# MkI.net
KiCad netlist of a schematic drawn in EAGLE
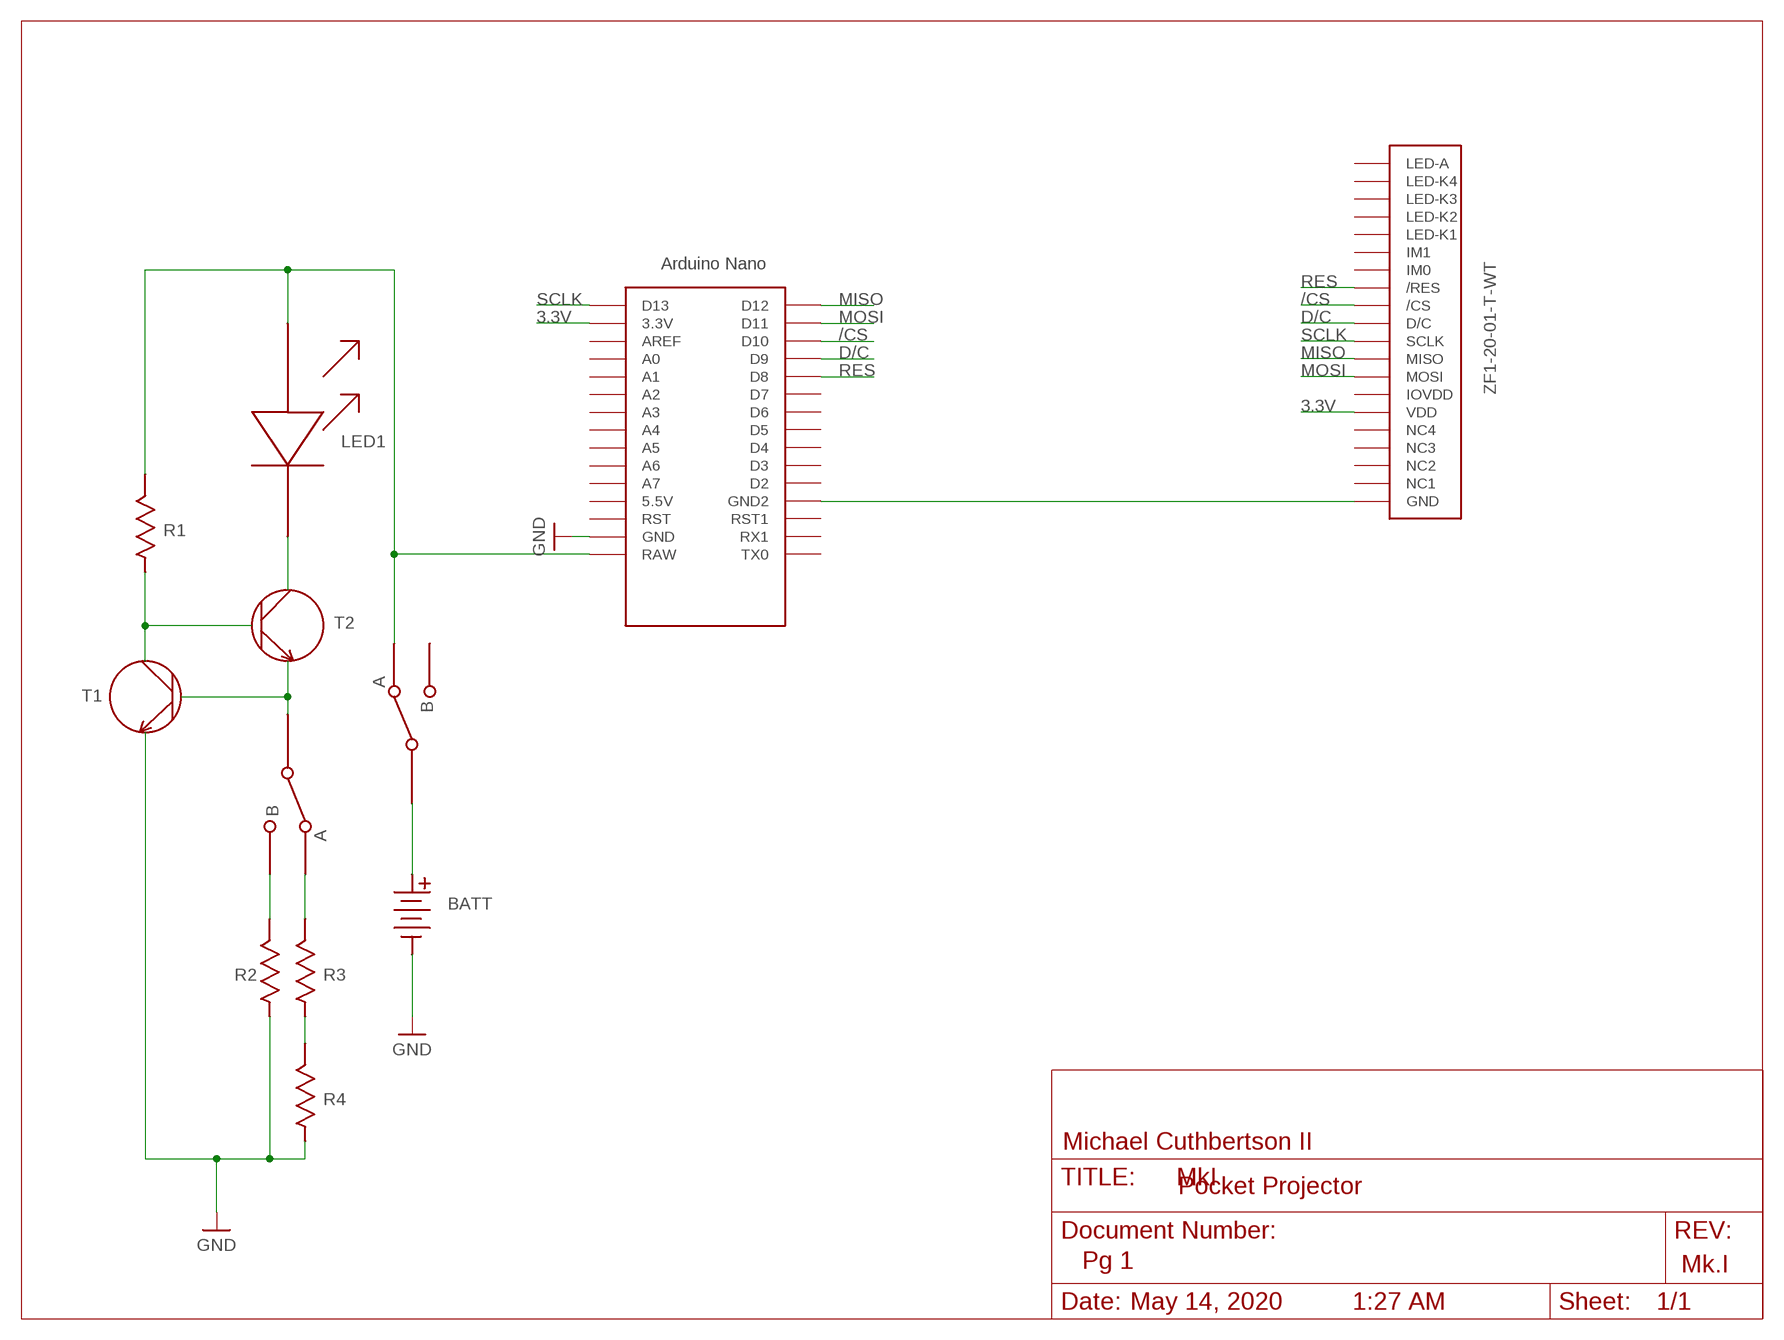
[diagram p0: schematic, sheet 1]

(export (version "E")
  (design (tool "Eeschema 10.0.6"))
  (components
    (comp (ref "R1")
      (value "2.2k")
      (footprint "eagle-import:ERJ1T")
      (libsource (lib "eagle-import") (part "ERJ1T"))
    )
    (comp (ref "R2")
      (value "130")
      (footprint "eagle-import:CRCW2512")
      (libsource (lib "eagle-import") (part "CRCW2512"))
    )
    (comp (ref "R3")
      (value "200")
      (footprint "eagle-import:CRCW2512")
      (libsource (lib "eagle-import") (part "CRCW2512"))
    )
    (comp (ref "R4")
      (value "200")
      (footprint "eagle-import:CRCW2512")
      (libsource (lib "eagle-import") (part "CRCW2512"))
    )
    (comp (ref "S1")
      (value "A107673-ND")
      (footprint "eagle-import:A107673-ND")
      (libsource (lib "eagle-import") (part "A107673-ND"))
    )
    (comp (ref "S2")
      (value "A107673-ND")
      (footprint "eagle-import:A107673-ND")
      (libsource (lib "eagle-import") (part "A107673-ND"))
    )
    (comp (ref "T1")
      (value "BC547")
      (footprint "eagle-import:BC547")
      (libsource (lib "eagle-import") (part "BC547"))
    )
    (comp (ref "T2")
      (value "BD139")
      (footprint "eagle-import:BD139")
      (libsource (lib "eagle-import") (part "BD139"))
    )
    (comp (ref "U$1")
      (value "NANO")
      (footprint "eagle-import:NANO")
      (libsource (lib "eagle-import") (part "NANO"))
    )
    (comp (ref "U$3")
      (value "XHGAWT-00-0000-00000HXE1")
      (footprint "eagle-import:XHGAWT-00-0000-00000HXE1")
      (libsource (lib "eagle-import") (part "XHGAWT-00-0000-00000HXE1"))
    )
    (comp (ref "U$5")
      (value "9v")
      (footprint "eagle-import:BATT")
      (libsource (lib "eagle-import") (part "BATT"))
    )
    (comp (ref "U$6")
      (value "ZF1-20-01-T-WT")
      (footprint "eagle-import:ZF1-20-01-T-WT")
      (libsource (lib "eagle-import") (part "ZF1-20-01-T-WT"))
    )
  )
  (nets
    (net (code "1") (name "/3.3V") (class "Default")
      (node (ref "U$1") (pin "3.3V") (pinfunction "3.3V_3.3V") (pintype "bidirectional"))
      (node (ref "U$6") (pin "VDD") (pinfunction "VDD_VDD") (pintype "bidirectional"))
    )
    (net (code "2") (name "/D{slash}C") (class "Default")
      (node (ref "U$1") (pin "D9") (pinfunction "D9_D9") (pintype "bidirectional"))
      (node (ref "U$6") (pin "D/C") (pinfunction "D/C_D/C") (pintype "bidirectional"))
    )
    (net (code "3") (name "/MISO") (class "Default")
      (node (ref "U$1") (pin "D12") (pinfunction "D12_D12") (pintype "bidirectional"))
      (node (ref "U$6") (pin "MISO") (pinfunction "MISO_MISO") (pintype "bidirectional"))
    )
    (net (code "4") (name "/MOSI") (class "Default")
      (node (ref "U$1") (pin "D11") (pinfunction "D11_D11") (pintype "bidirectional"))
      (node (ref "U$6") (pin "MOSI") (pinfunction "MOSI_MOSI") (pintype "bidirectional"))
    )
    (net (code "5") (name "/RES") (class "Default")
      (node (ref "U$1") (pin "D8") (pinfunction "D8_D8") (pintype "bidirectional"))
      (node (ref "U$6") (pin "/RES") (pinfunction "/RES_/RES") (pintype "bidirectional"))
    )
    (net (code "6") (name "/SCLK") (class "Default")
      (node (ref "U$1") (pin "D13") (pinfunction "D13_D13") (pintype "bidirectional"))
      (node (ref "U$6") (pin "SCLK") (pinfunction "SCLK_SCLK") (pintype "bidirectional"))
    )
    (net (code "7") (name "/{slash}CS") (class "Default")
      (node (ref "U$1") (pin "D10") (pinfunction "D10_D10") (pintype "bidirectional"))
      (node (ref "U$6") (pin "/CS") (pinfunction "/CS_/CS") (pintype "bidirectional"))
    )
    (net (code "8") (name "GND") (class "Default")
      (node (ref "R2") (pin "P$1") (pinfunction "P$1_P$1") (pintype "bidirectional"))
      (node (ref "R4") (pin "P$1") (pinfunction "P$1_P$1") (pintype "bidirectional"))
      (node (ref "T1") (pin "P$3") (pinfunction "P$3_P$3") (pintype "bidirectional"))
      (node (ref "U$1") (pin "GND") (pinfunction "GND_GND") (pintype "bidirectional"))
      (node (ref "U$5") (pin "GND") (pinfunction "GND_GND") (pintype "power_in"))
    )
    (net (code "9") (name "Net-(R1-PadP$1)") (class "Default")
      (node (ref "R1") (pin "P$1") (pinfunction "P$1_P$1") (pintype "bidirectional"))
      (node (ref "T1") (pin "P$2") (pinfunction "P$2_P$2") (pintype "bidirectional"))
      (node (ref "T2") (pin "P$1") (pinfunction "P$1_P$1") (pintype "bidirectional"))
    )
    (net (code "10") (name "Net-(R1-PadP$2)") (class "Default")
      (node (ref "R1") (pin "P$2") (pinfunction "P$2_P$2") (pintype "bidirectional"))
      (node (ref "S1") (pin "P$2") (pinfunction "P$2_P$2") (pintype "bidirectional"))
      (node (ref "U$1") (pin "RAW") (pinfunction "RAW_RAW") (pintype "bidirectional"))
      (node (ref "U$3") (pin "P$2") (pinfunction "P$2_P$2") (pintype "power_in"))
    )
    (net (code "11") (name "Net-(R2-PadP$2)") (class "Default")
      (node (ref "R2") (pin "P$2") (pinfunction "P$2_P$2") (pintype "bidirectional"))
      (node (ref "S2") (pin "P$3") (pinfunction "P$3_P$3") (pintype "bidirectional"))
    )
    (net (code "12") (name "Net-(R3-PadP$1)") (class "Default")
      (node (ref "R3") (pin "P$1") (pinfunction "P$1_P$1") (pintype "bidirectional"))
      (node (ref "R4") (pin "P$2") (pinfunction "P$2_P$2") (pintype "bidirectional"))
    )
    (net (code "13") (name "Net-(R3-PadP$2)") (class "Default")
      (node (ref "R3") (pin "P$2") (pinfunction "P$2_P$2") (pintype "bidirectional"))
      (node (ref "S2") (pin "P$2") (pinfunction "P$2_P$2") (pintype "bidirectional"))
    )
    (net (code "14") (name "Net-(S1-PadP$1)") (class "Default")
      (node (ref "S1") (pin "P$1") (pinfunction "P$1_P$1") (pintype "bidirectional"))
      (node (ref "U$5") (pin "VCC") (pinfunction "VCC_VCC") (pintype "power_in"))
    )
    (net (code "15") (name "Net-(S2-PadP$1)") (class "Default")
      (node (ref "S2") (pin "P$1") (pinfunction "P$1_P$1") (pintype "bidirectional"))
      (node (ref "T1") (pin "P$1") (pinfunction "P$1_P$1") (pintype "bidirectional"))
      (node (ref "T2") (pin "P$3") (pinfunction "P$3_P$3") (pintype "bidirectional"))
    )
    (net (code "16") (name "Net-(T2-PadP$2)") (class "Default")
      (node (ref "T2") (pin "P$2") (pinfunction "P$2_P$2") (pintype "bidirectional"))
      (node (ref "U$3") (pin "P$1") (pinfunction "P$1_P$1") (pintype "power_in"))
    )
    (net (code "17") (name "Net-(U$1-GND2)") (class "Default")
      (node (ref "U$1") (pin "GND1") (pinfunction "GND2_GND1") (pintype "bidirectional"))
      (node (ref "U$6") (pin "GND") (pinfunction "GND_GND") (pintype "bidirectional"))
    )
    (net (code "18") (name "unconnected-(S1-PadP$3)") (class "Default")
      (node (ref "S1") (pin "P$3") (pinfunction "P$3_P$3") (pintype "bidirectional"))
    )
    (net (code "19") (name "unconnected-(U$1-5.5V-Pad5V)") (class "Default")
      (node (ref "U$1") (pin "5V") (pinfunction "5.5V_5V") (pintype "bidirectional"))
    )
    (net (code "20") (name "unconnected-(U$1-PadA0)") (class "Default")
      (node (ref "U$1") (pin "A0") (pinfunction "A0_A0") (pintype "bidirectional"))
    )
    (net (code "21") (name "unconnected-(U$1-PadA1)") (class "Default")
      (node (ref "U$1") (pin "A1") (pinfunction "A1_A1") (pintype "bidirectional"))
    )
    (net (code "22") (name "unconnected-(U$1-PadA2)") (class "Default")
      (node (ref "U$1") (pin "A2") (pinfunction "A2_A2") (pintype "bidirectional"))
    )
    (net (code "23") (name "unconnected-(U$1-PadA3)") (class "Default")
      (node (ref "U$1") (pin "A3") (pinfunction "A3_A3") (pintype "bidirectional"))
    )
    (net (code "24") (name "unconnected-(U$1-PadA4)") (class "Default")
      (node (ref "U$1") (pin "A4") (pinfunction "A4_A4") (pintype "bidirectional"))
    )
    (net (code "25") (name "unconnected-(U$1-PadA5)") (class "Default")
      (node (ref "U$1") (pin "A5") (pinfunction "A5_A5") (pintype "bidirectional"))
    )
    (net (code "26") (name "unconnected-(U$1-PadA6)") (class "Default")
      (node (ref "U$1") (pin "A6") (pinfunction "A6_A6") (pintype "bidirectional"))
    )
    (net (code "27") (name "unconnected-(U$1-PadA7)") (class "Default")
      (node (ref "U$1") (pin "A7") (pinfunction "A7_A7") (pintype "bidirectional"))
    )
    (net (code "28") (name "unconnected-(U$1-PadAREF)") (class "Default")
      (node (ref "U$1") (pin "AREF") (pinfunction "AREF_AREF") (pintype "bidirectional"))
    )
    (net (code "29") (name "unconnected-(U$1-PadD2)") (class "Default")
      (node (ref "U$1") (pin "D2") (pinfunction "D2_D2") (pintype "bidirectional"))
    )
    (net (code "30") (name "unconnected-(U$1-PadD3)") (class "Default")
      (node (ref "U$1") (pin "D3") (pinfunction "D3_D3") (pintype "bidirectional"))
    )
    (net (code "31") (name "unconnected-(U$1-PadD4)") (class "Default")
      (node (ref "U$1") (pin "D4") (pinfunction "D4_D4") (pintype "bidirectional"))
    )
    (net (code "32") (name "unconnected-(U$1-PadD5)") (class "Default")
      (node (ref "U$1") (pin "D5") (pinfunction "D5_D5") (pintype "bidirectional"))
    )
    (net (code "33") (name "unconnected-(U$1-PadD6)") (class "Default")
      (node (ref "U$1") (pin "D6") (pinfunction "D6_D6") (pintype "bidirectional"))
    )
    (net (code "34") (name "unconnected-(U$1-PadD7)") (class "Default")
      (node (ref "U$1") (pin "D7") (pinfunction "D7_D7") (pintype "bidirectional"))
    )
    (net (code "35") (name "unconnected-(U$1-PadICSP1)") (class "Default")
      (node (ref "U$1") (pin "ICSP1") (pinfunction "ICSP1_ICSP1") (pintype "bidirectional"))
    )
    (net (code "36") (name "unconnected-(U$1-PadICSP2)") (class "Default")
      (node (ref "U$1") (pin "ICSP2") (pinfunction "ICSP2_ICSP2") (pintype "bidirectional"))
    )
    (net (code "37") (name "unconnected-(U$1-PadICSP3)") (class "Default")
      (node (ref "U$1") (pin "ICSP3") (pinfunction "ICSP3_ICSP3") (pintype "bidirectional"))
    )
    (net (code "38") (name "unconnected-(U$1-PadICSP4)") (class "Default")
      (node (ref "U$1") (pin "ICSP4") (pinfunction "ICSP4_ICSP4") (pintype "bidirectional"))
    )
    (net (code "39") (name "unconnected-(U$1-PadICSP5)") (class "Default")
      (node (ref "U$1") (pin "ICSP5") (pinfunction "ICSP5_ICSP5") (pintype "bidirectional"))
    )
    (net (code "40") (name "unconnected-(U$1-PadICSP6)") (class "Default")
      (node (ref "U$1") (pin "ICSP6") (pinfunction "ICSP6_ICSP6") (pintype "bidirectional"))
    )
    (net (code "41") (name "unconnected-(U$1-PadRST)") (class "Default")
      (node (ref "U$1") (pin "RST") (pinfunction "RST_RST") (pintype "bidirectional"))
    )
    (net (code "42") (name "unconnected-(U$1-PadRST1)") (class "Default")
      (node (ref "U$1") (pin "RST1") (pinfunction "RST1_RST1") (pintype "bidirectional"))
    )
    (net (code "43") (name "unconnected-(U$1-PadRX1)") (class "Default")
      (node (ref "U$1") (pin "RX1") (pinfunction "RX1_RX1") (pintype "bidirectional"))
    )
    (net (code "44") (name "unconnected-(U$1-PadTX0)") (class "Default")
      (node (ref "U$1") (pin "TX0") (pinfunction "TX0_TX0") (pintype "bidirectional"))
    )
    (net (code "45") (name "unconnected-(U$6-PadIM0)") (class "Default")
      (node (ref "U$6") (pin "IM0") (pinfunction "IM0_IM0") (pintype "bidirectional"))
    )
    (net (code "46") (name "unconnected-(U$6-PadIM1)") (class "Default")
      (node (ref "U$6") (pin "IM1") (pinfunction "IM1_IM1") (pintype "bidirectional"))
    )
    (net (code "47") (name "unconnected-(U$6-PadIOVDD)") (class "Default")
      (node (ref "U$6") (pin "IOVDD") (pinfunction "IOVDD_IOVDD") (pintype "bidirectional"))
    )
    (net (code "48") (name "unconnected-(U$6-PadLED-A)") (class "Default")
      (node (ref "U$6") (pin "LED-A") (pinfunction "LED-A_LED-A") (pintype "bidirectional"))
    )
    (net (code "49") (name "unconnected-(U$6-PadLED-K1)") (class "Default")
      (node (ref "U$6") (pin "LED-K1") (pinfunction "LED-K1_LED-K1") (pintype "bidirectional"))
    )
    (net (code "50") (name "unconnected-(U$6-PadLED-K2)") (class "Default")
      (node (ref "U$6") (pin "LED-K2") (pinfunction "LED-K2_LED-K2") (pintype "bidirectional"))
    )
    (net (code "51") (name "unconnected-(U$6-PadLED-K3)") (class "Default")
      (node (ref "U$6") (pin "LED-K3") (pinfunction "LED-K3_LED-K3") (pintype "bidirectional"))
    )
    (net (code "52") (name "unconnected-(U$6-PadLED-K4)") (class "Default")
      (node (ref "U$6") (pin "LED-K4") (pinfunction "LED-K4_LED-K4") (pintype "bidirectional"))
    )
    (net (code "53") (name "unconnected-(U$6-PadNC1)") (class "Default")
      (node (ref "U$6") (pin "NC1") (pinfunction "NC1_NC1") (pintype "bidirectional"))
    )
    (net (code "54") (name "unconnected-(U$6-PadNC2)") (class "Default")
      (node (ref "U$6") (pin "NC2") (pinfunction "NC2_NC2") (pintype "bidirectional"))
    )
    (net (code "55") (name "unconnected-(U$6-PadNC3)") (class "Default")
      (node (ref "U$6") (pin "NC3") (pinfunction "NC3_NC3") (pintype "bidirectional"))
    )
    (net (code "56") (name "unconnected-(U$6-PadNC4)") (class "Default")
      (node (ref "U$6") (pin "NC4") (pinfunction "NC4_NC4") (pintype "bidirectional"))
    )
  )
)
